# midimixer-channel.net
KiCad netlist of a schematic drawn in EAGLE
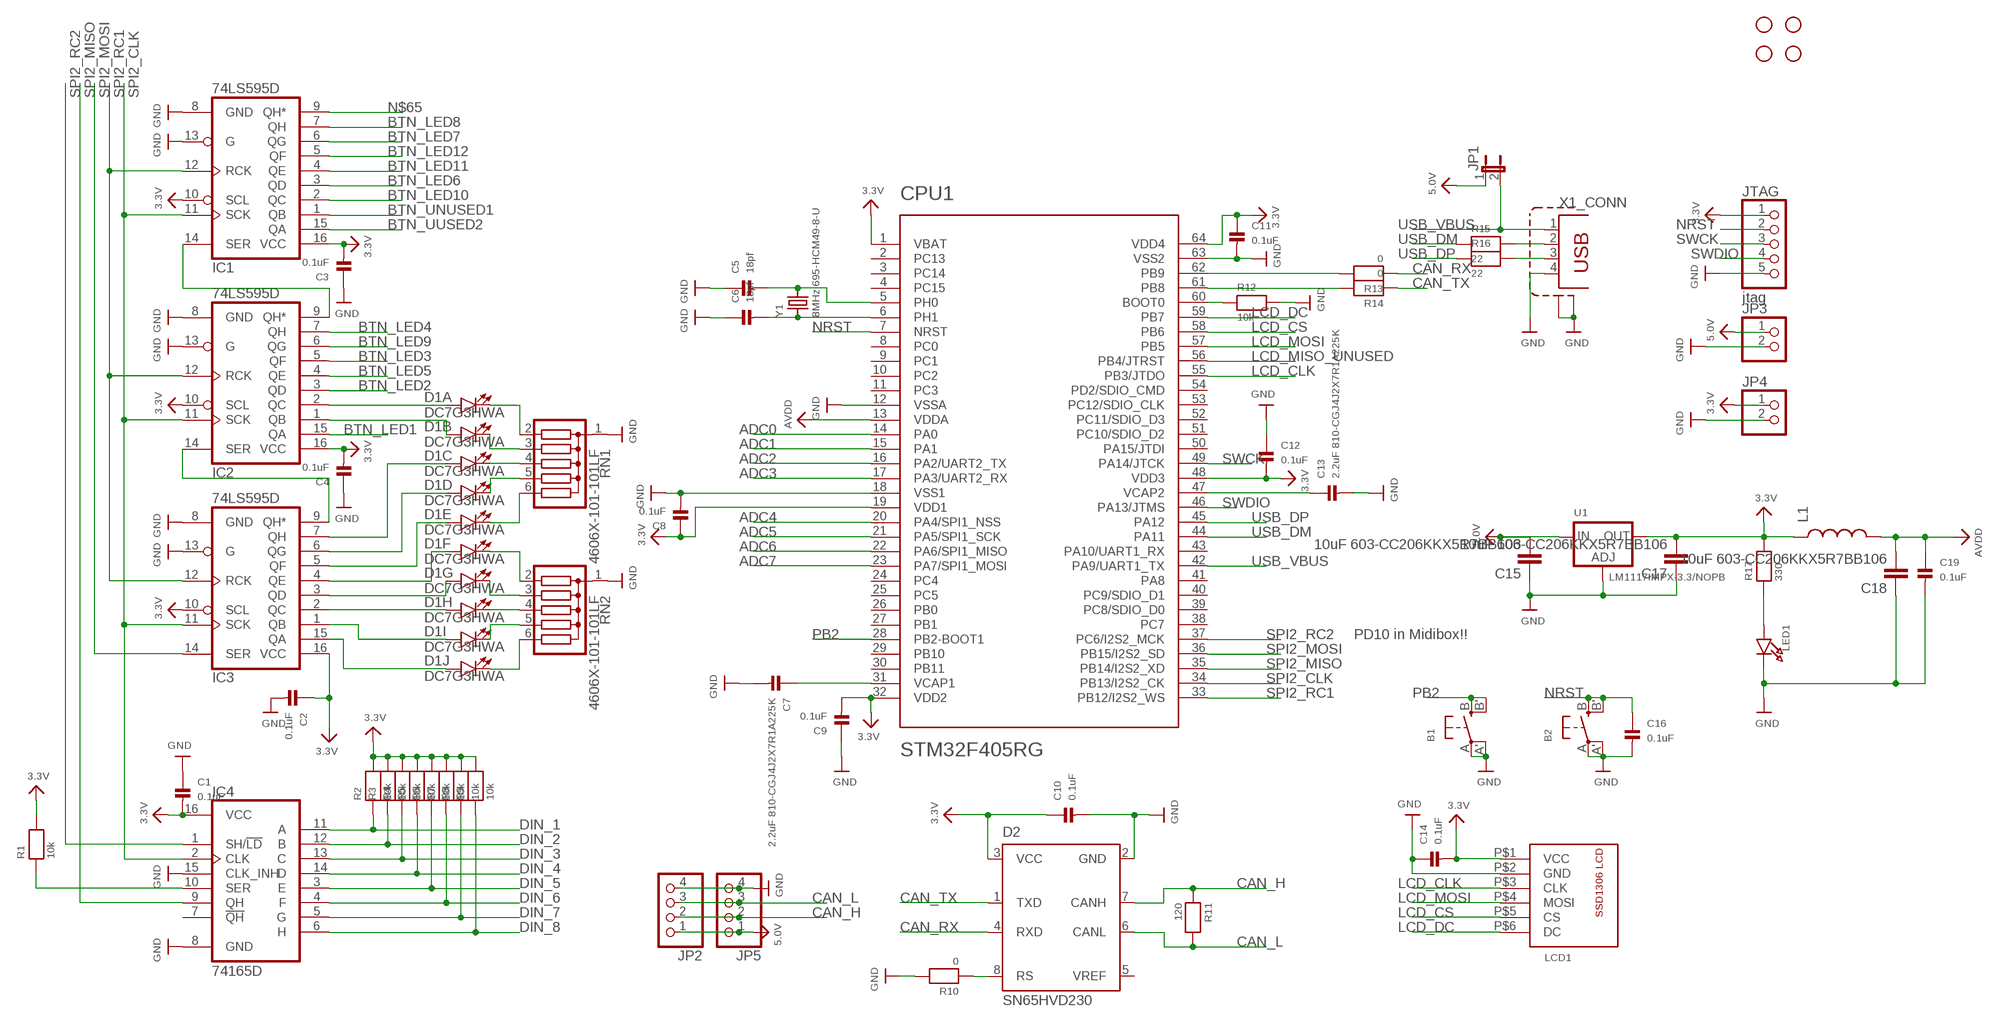
[diagram p0: schematic, sheet 1]
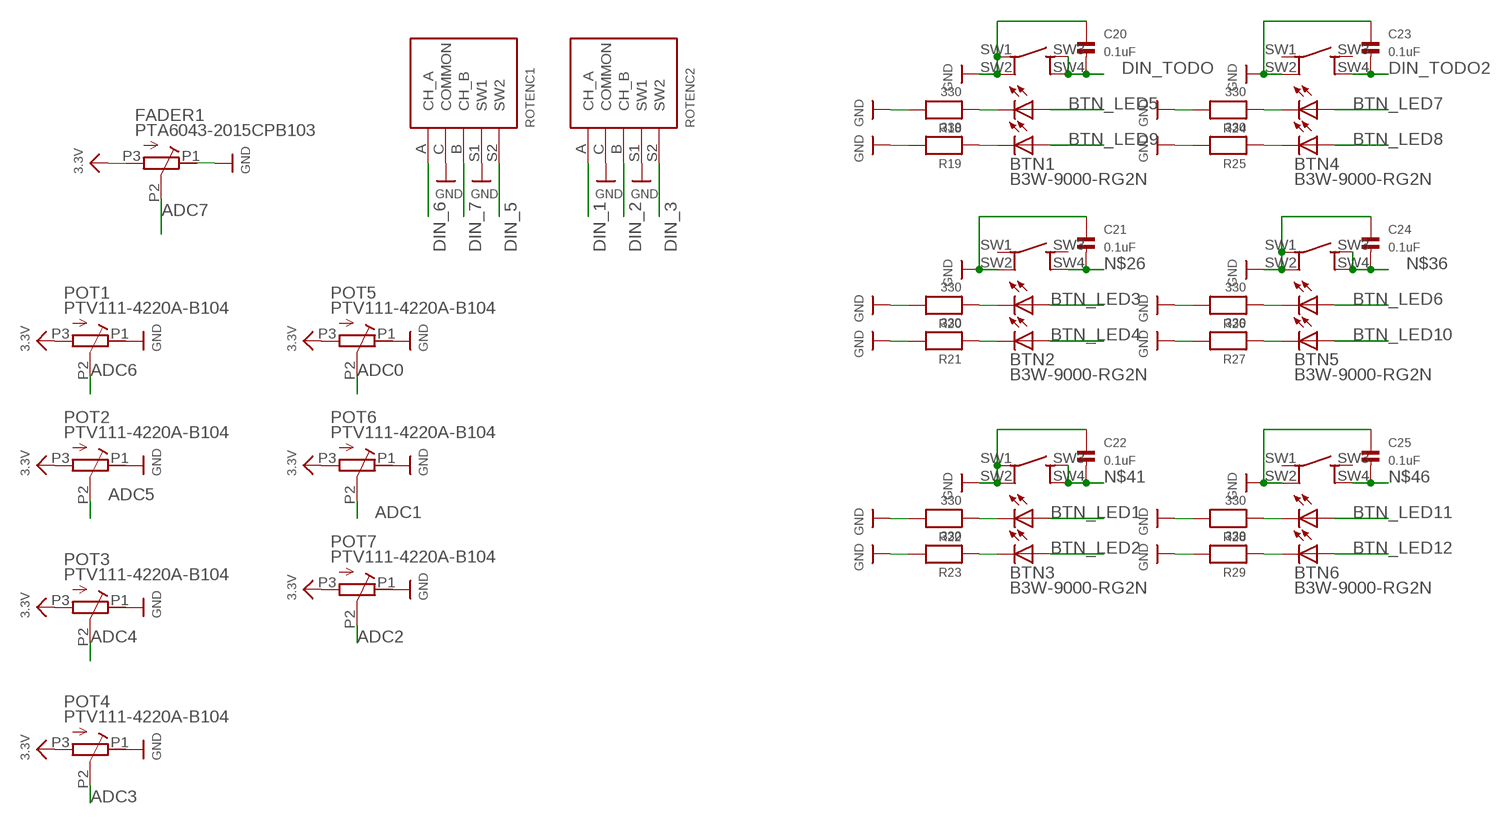
[diagram p1: schematic, sheet 2]

(export (version "E")
  (design (tool "Eeschema 10.0.6"))
  (components
    (comp (ref "B1")
      (value "SWITCH_TACT_SMT")
      (footprint "eagle-import:EVQ-Q2")
      (libsource (lib "eagle-import") (part "SWITCH_TACT_SMT"))
    )
    (comp (ref "B2")
      (value "SWITCH_TACT_SMT")
      (footprint "eagle-import:EVQ-Q2")
      (libsource (lib "eagle-import") (part "SWITCH_TACT_SMT"))
    )
    (comp (ref "C1")
      (value "0.1uF")
      (footprint "eagle-import:0603")
      (libsource (lib "eagle-import") (part "CAP_CERAMIC0603"))
    )
    (comp (ref "C2")
      (value "0.1uF")
      (footprint "eagle-import:0603")
      (libsource (lib "eagle-import") (part "CAP_CERAMIC0603"))
    )
    (comp (ref "C3")
      (value "0.1uF")
      (footprint "eagle-import:0603")
      (libsource (lib "eagle-import") (part "CAP_CERAMIC0603"))
    )
    (comp (ref "C4")
      (value "0.1uF")
      (footprint "eagle-import:0603")
      (libsource (lib "eagle-import") (part "CAP_CERAMIC0603"))
    )
    (comp (ref "C5")
      (value "18pf")
      (footprint "eagle-import:0603")
      (libsource (lib "eagle-import") (part "CAP_CERAMIC0603"))
    )
    (comp (ref "C6")
      (value "18pf")
      (footprint "eagle-import:0603")
      (libsource (lib "eagle-import") (part "CAP_CERAMIC0603"))
    )
    (comp (ref "C7")
      (value "2.2uF 810-CGJ4J2X7R1A225K")
      (footprint "eagle-import:0805")
      (libsource (lib "eagle-import") (part "CAP_CERAMIC0805"))
    )
    (comp (ref "C8")
      (value "0.1uF")
      (footprint "eagle-import:0603")
      (libsource (lib "eagle-import") (part "CAP_CERAMIC0603"))
    )
    (comp (ref "C9")
      (value "0.1uF")
      (footprint "eagle-import:0603")
      (libsource (lib "eagle-import") (part "CAP_CERAMIC0603"))
    )
    (comp (ref "C10")
      (value "0.1uF")
      (footprint "eagle-import:0603")
      (libsource (lib "eagle-import") (part "CAP_CERAMIC0603"))
    )
    (comp (ref "C11")
      (value "0.1uF")
      (footprint "eagle-import:0603")
      (libsource (lib "eagle-import") (part "CAP_CERAMIC0603"))
    )
    (comp (ref "C12")
      (value "0.1uF")
      (footprint "eagle-import:0603")
      (libsource (lib "eagle-import") (part "CAP_CERAMIC0603"))
    )
    (comp (ref "C13")
      (value "2.2uF 810-CGJ4J2X7R1A225K")
      (footprint "eagle-import:0805")
      (libsource (lib "eagle-import") (part "CAP_CERAMIC0805"))
    )
    (comp (ref "C14")
      (value "0.1uF")
      (footprint "eagle-import:0603")
      (libsource (lib "eagle-import") (part "CAP_CERAMIC0603"))
    )
    (comp (ref "C15")
      (value "10uF 603-CC206KKX5R7BB106")
      (footprint "eagle-import:1206")
      (libsource (lib "eagle-import") (part "CAP1206"))
    )
    (comp (ref "C16")
      (value "0.1uF")
      (footprint "eagle-import:0603")
      (libsource (lib "eagle-import") (part "CAP_CERAMIC0603"))
    )
    (comp (ref "C17")
      (value "10uF 603-CC206KKX5R7BB106")
      (footprint "eagle-import:1206")
      (libsource (lib "eagle-import") (part "CAP1206"))
    )
    (comp (ref "C18")
      (value "10uF 603-CC206KKX5R7BB106")
      (footprint "eagle-import:1206")
      (libsource (lib "eagle-import") (part "CAP1206"))
    )
    (comp (ref "C19")
      (value "0.1uF")
      (footprint "eagle-import:0603")
      (libsource (lib "eagle-import") (part "CAP_CERAMIC0603"))
    )
    (comp (ref "CPU1")
      (value "STM32F405RG")
      (footprint "eagle-import:TQFP64")
      (libsource (lib "eagle-import") (part "STM32F405RG"))
    )
    (comp (ref "D1")
      (value "DC7G3HWA")
      (footprint "eagle-import:LED_BARGAPH_10")
      (libsource (lib "eagle-import") (part "LED_BARGRAPH_10"))
    )
    (comp (ref "D2")
      (value "SN65HVD230")
      (footprint "eagle-import:SO8")
      (libsource (lib "eagle-import") (part "SN65HVD230"))
    )
    (comp (ref "H1")
      (value "STAND-OFF")
      (footprint "eagle-import:STAND-OFF")
      (libsource (lib "eagle-import") (part "STAND-OFF"))
    )
    (comp (ref "H2")
      (value "STAND-OFF")
      (footprint "eagle-import:STAND-OFF")
      (libsource (lib "eagle-import") (part "STAND-OFF"))
    )
    (comp (ref "H3")
      (value "STAND-OFF")
      (footprint "eagle-import:STAND-OFF")
      (libsource (lib "eagle-import") (part "STAND-OFF"))
    )
    (comp (ref "H4")
      (value "STAND-OFF")
      (footprint "eagle-import:STAND-OFF")
      (libsource (lib "eagle-import") (part "STAND-OFF"))
    )
    (comp (ref "IC1")
      (value "74LS595D")
      (footprint "eagle-import:SO16")
      (libsource (lib "eagle-import") (part "74595DLS"))
    )
    (comp (ref "IC2")
      (value "74LS595D")
      (footprint "eagle-import:SO16")
      (libsource (lib "eagle-import") (part "74595DLS"))
    )
    (comp (ref "IC3")
      (value "74LS595D")
      (footprint "eagle-import:SO16")
      (libsource (lib "eagle-import") (part "74595DLS"))
    )
    (comp (ref "IC4")
      (value "74165D")
      (footprint "eagle-import:SO16")
      (libsource (lib "eagle-import") (part "74165D"))
    )
    (comp (ref "JP1")
      (value "JUMPER2")
      (footprint "eagle-import:JUMPER2")
      (libsource (lib "eagle-import") (part "JUMPER2"))
    )
    (comp (ref "JP2")
      (value "HEADER-1X4ROUND")
      (footprint "eagle-import:1X04_ROUND")
      (libsource (lib "eagle-import") (part "HEADER-1X4ROUND"))
    )
    (comp (ref "JP3")
      (value "HEADER-1X2ROUND")
      (footprint "eagle-import:1X02_ROUND")
      (libsource (lib "eagle-import") (part "HEADER-1X2ROUND"))
    )
    (comp (ref "JP4")
      (value "HEADER-1X2ROUND")
      (footprint "eagle-import:1X02_ROUND")
      (libsource (lib "eagle-import") (part "HEADER-1X2ROUND"))
    )
    (comp (ref "JP5")
      (value "HEADER-1X4ROUND")
      (footprint "eagle-import:1X04_ROUND")
      (libsource (lib "eagle-import") (part "HEADER-1X4ROUND"))
    )
    (comp (ref "JTAG")
      (value "jtag")
      (footprint "eagle-import:1X05_ROUND_76")
      (libsource (lib "eagle-import") (part "HEADER-1X576MIL"))
    )
    (comp (ref "L1")
      (value "INDUCTOR0805")
      (footprint "eagle-import:0805")
      (libsource (lib "eagle-import") (part "INDUCTOR0805"))
    )
    (comp (ref "LCD1")
      (value "SSD1306-ALI")
      (footprint "eagle-import:SSD1306-ALI")
      (libsource (lib "eagle-import") (part "SSD1306-ALI"))
    )
    (comp (ref "LED1")
      (value "LED0603")
      (footprint "eagle-import:CHIPLED_0603")
      (libsource (lib "eagle-import") (part "LED0603"))
    )
    (comp (ref "R1")
      (value "10k")
      (footprint "eagle-import:_0603")
      (libsource (lib "eagle-import") (part "RESISTOR_0603"))
    )
    (comp (ref "R2")
      (value "10k")
      (footprint "eagle-import:_0603")
      (libsource (lib "eagle-import") (part "RESISTOR_0603"))
    )
    (comp (ref "R3")
      (value "10k")
      (footprint "eagle-import:_0603")
      (libsource (lib "eagle-import") (part "RESISTOR_0603"))
    )
    (comp (ref "R4")
      (value "10k")
      (footprint "eagle-import:_0603")
      (libsource (lib "eagle-import") (part "RESISTOR_0603"))
    )
    (comp (ref "R5")
      (value "10k")
      (footprint "eagle-import:_0603")
      (libsource (lib "eagle-import") (part "RESISTOR_0603"))
    )
    (comp (ref "R6")
      (value "10k")
      (footprint "eagle-import:_0603")
      (libsource (lib "eagle-import") (part "RESISTOR_0603"))
    )
    (comp (ref "R7")
      (value "10k")
      (footprint "eagle-import:_0603")
      (libsource (lib "eagle-import") (part "RESISTOR_0603"))
    )
    (comp (ref "R8")
      (value "10k")
      (footprint "eagle-import:_0603")
      (libsource (lib "eagle-import") (part "RESISTOR_0603"))
    )
    (comp (ref "R9")
      (value "10k")
      (footprint "eagle-import:_0603")
      (libsource (lib "eagle-import") (part "RESISTOR_0603"))
    )
    (comp (ref "R10")
      (value "0")
      (footprint "eagle-import:_0603")
      (libsource (lib "eagle-import") (part "RESISTOR_0603"))
    )
    (comp (ref "R11")
      (value "120")
      (footprint "eagle-import:_0603")
      (libsource (lib "eagle-import") (part "RESISTOR_0603"))
    )
    (comp (ref "R12")
      (value "10k")
      (footprint "eagle-import:_0603")
      (libsource (lib "eagle-import") (part "RESISTOR_0603"))
    )
    (comp (ref "R13")
      (value "0")
      (footprint "eagle-import:_0603")
      (libsource (lib "eagle-import") (part "RESISTOR_0603"))
    )
    (comp (ref "R14")
      (value "0")
      (footprint "eagle-import:_0603")
      (libsource (lib "eagle-import") (part "RESISTOR_0603"))
    )
    (comp (ref "R15")
      (value "22")
      (footprint "eagle-import:0603")
      (libsource (lib "eagle-import") (part "RESISTOR0603"))
    )
    (comp (ref "R16")
      (value "22")
      (footprint "eagle-import:0603")
      (libsource (lib "eagle-import") (part "RESISTOR0603"))
    )
    (comp (ref "R17")
      (value "330")
      (footprint "eagle-import:0603")
      (libsource (lib "eagle-import") (part "RESISTOR0603"))
    )
    (comp (ref "RN1")
      (value "4606X-101-101LF")
      (footprint "eagle-import:SIL6")
      (libsource (lib "eagle-import") (part "G05R"))
    )
    (comp (ref "RN2")
      (value "4606X-101-101LF")
      (footprint "eagle-import:SIL6")
      (libsource (lib "eagle-import") (part "G05R"))
    )
    (comp (ref "U1")
      (value "LM1117IMPX-3.3/NOPB")
      (footprint "eagle-import:SOT223-R")
      (libsource (lib "eagle-import") (part "LM1117SOT223-REFLOW"))
    )
    (comp (ref "X1")
      (value "TE-292304-1")
      (footprint "eagle-import:TE-292304-1")
      (libsource (lib "eagle-import") (part "TE-292304-1"))
    )
    (comp (ref "Y1")
      (value "8MHz 695-HCM49-8-U")
      (footprint "eagle-import:HC49UP")
      (libsource (lib "eagle-import") (part "CRYSTALSMD"))
    )
    (comp (ref "BTN1")
      (value "B3W-9000-RG2N")
      (footprint "eagle-import:B3W-9000-X2X")
      (libsource (lib "eagle-import") (part "B3W-9000-RG2N"))
    )
    (comp (ref "BTN2")
      (value "B3W-9000-RG2N")
      (footprint "eagle-import:B3W-9000-X2X")
      (libsource (lib "eagle-import") (part "B3W-9000-RG2N"))
    )
    (comp (ref "BTN3")
      (value "B3W-9000-RG2N")
      (footprint "eagle-import:B3W-9000-X2X")
      (libsource (lib "eagle-import") (part "B3W-9000-RG2N"))
    )
    (comp (ref "BTN4")
      (value "B3W-9000-RG2N")
      (footprint "eagle-import:B3W-9000-X2X")
      (libsource (lib "eagle-import") (part "B3W-9000-RG2N"))
    )
    (comp (ref "BTN5")
      (value "B3W-9000-RG2N")
      (footprint "eagle-import:B3W-9000-X2X")
      (libsource (lib "eagle-import") (part "B3W-9000-RG2N"))
    )
    (comp (ref "BTN6")
      (value "B3W-9000-RG2N")
      (footprint "eagle-import:B3W-9000-X2X")
      (libsource (lib "eagle-import") (part "B3W-9000-RG2N"))
    )
    (comp (ref "C20")
      (value "0.1uF")
      (footprint "eagle-import:0603")
      (libsource (lib "eagle-import") (part "CAP_CERAMIC0603"))
    )
    (comp (ref "C21")
      (value "0.1uF")
      (footprint "eagle-import:0603")
      (libsource (lib "eagle-import") (part "CAP_CERAMIC0603"))
    )
    (comp (ref "C22")
      (value "0.1uF")
      (footprint "eagle-import:0603")
      (libsource (lib "eagle-import") (part "CAP_CERAMIC0603"))
    )
    (comp (ref "C23")
      (value "0.1uF")
      (footprint "eagle-import:0603")
      (libsource (lib "eagle-import") (part "CAP_CERAMIC0603"))
    )
    (comp (ref "C24")
      (value "0.1uF")
      (footprint "eagle-import:0603")
      (libsource (lib "eagle-import") (part "CAP_CERAMIC0603"))
    )
    (comp (ref "C25")
      (value "0.1uF")
      (footprint "eagle-import:0603")
      (libsource (lib "eagle-import") (part "CAP_CERAMIC0603"))
    )
    (comp (ref "FADER1")
      (value "PTA6043-2015CPB103")
      (footprint "eagle-import:PTA6043-2015CPB103")
      (libsource (lib "eagle-import") (part "PTA6043-2015CPB103"))
    )
    (comp (ref "POT1")
      (value "PTV111-4220A-B104")
      (footprint "eagle-import:PTV111-4")
      (libsource (lib "eagle-import") (part "PTV111-4220A-B104"))
    )
    (comp (ref "POT2")
      (value "PTV111-4220A-B104")
      (footprint "eagle-import:PTV111-4")
      (libsource (lib "eagle-import") (part "PTV111-4220A-B104"))
    )
    (comp (ref "POT3")
      (value "PTV111-4220A-B104")
      (footprint "eagle-import:PTV111-4")
      (libsource (lib "eagle-import") (part "PTV111-4220A-B104"))
    )
    (comp (ref "POT4")
      (value "PTV111-4220A-B104")
      (footprint "eagle-import:PTV111-4")
      (libsource (lib "eagle-import") (part "PTV111-4220A-B104"))
    )
    (comp (ref "POT5")
      (value "PTV111-4220A-B104")
      (footprint "eagle-import:PTV111-4")
      (libsource (lib "eagle-import") (part "PTV111-4220A-B104"))
    )
    (comp (ref "POT6")
      (value "PTV111-4220A-B104")
      (footprint "eagle-import:PTV111-4")
      (libsource (lib "eagle-import") (part "PTV111-4220A-B104"))
    )
    (comp (ref "POT7")
      (value "PTV111-4220A-B104")
      (footprint "eagle-import:PTV111-4")
      (libsource (lib "eagle-import") (part "PTV111-4220A-B104"))
    )
    (comp (ref "R18")
      (value "330")
      (footprint "eagle-import:0603")
      (libsource (lib "eagle-import") (part "RESISTOR0603"))
    )
    (comp (ref "R19")
      (value "330")
      (footprint "eagle-import:0603")
      (libsource (lib "eagle-import") (part "RESISTOR0603"))
    )
    (comp (ref "R20")
      (value "330")
      (footprint "eagle-import:0603")
      (libsource (lib "eagle-import") (part "RESISTOR0603"))
    )
    (comp (ref "R21")
      (value "330")
      (footprint "eagle-import:0603")
      (libsource (lib "eagle-import") (part "RESISTOR0603"))
    )
    (comp (ref "R22")
      (value "330")
      (footprint "eagle-import:0603")
      (libsource (lib "eagle-import") (part "RESISTOR0603"))
    )
    (comp (ref "R23")
      (value "330")
      (footprint "eagle-import:0603")
      (libsource (lib "eagle-import") (part "RESISTOR0603"))
    )
    (comp (ref "R24")
      (value "330")
      (footprint "eagle-import:0603")
      (libsource (lib "eagle-import") (part "RESISTOR0603"))
    )
    (comp (ref "R25")
      (value "330")
      (footprint "eagle-import:0603")
      (libsource (lib "eagle-import") (part "RESISTOR0603"))
    )
    (comp (ref "R26")
      (value "330")
      (footprint "eagle-import:0603")
      (libsource (lib "eagle-import") (part "RESISTOR0603"))
    )
    (comp (ref "R27")
      (value "330")
      (footprint "eagle-import:0603")
      (libsource (lib "eagle-import") (part "RESISTOR0603"))
    )
    (comp (ref "R28")
      (value "330")
      (footprint "eagle-import:0603")
      (libsource (lib "eagle-import") (part "RESISTOR0603"))
    )
    (comp (ref "R29")
      (value "330")
      (footprint "eagle-import:0603")
      (libsource (lib "eagle-import") (part "RESISTOR0603"))
    )
    (comp (ref "ROTENC1")
      (value "PEC11-4215K-S0024")
      (footprint "eagle-import:PEC111-4XXXK-SXXXX")
      (libsource (lib "eagle-import") (part "PEC11-4215K-S0024"))
    )
    (comp (ref "ROTENC2")
      (value "PEC11-4215K-S0024")
      (footprint "eagle-import:PEC111-4XXXK-SXXXX")
      (libsource (lib "eagle-import") (part "PEC11-4215K-S0024"))
    )
  )
  (nets
    (net (code "1") (name "3.3V") (class "Default")
      (node (ref "C1") (pin "2") (pinfunction "P$2_2") (pintype "passive"))
      (node (ref "C10") (pin "1") (pinfunction "P$1_1") (pintype "passive"))
      (node (ref "C11") (pin "1") (pinfunction "P$1_1") (pintype "passive"))
      (node (ref "C12") (pin "2") (pinfunction "P$2_2") (pintype "passive"))
      (node (ref "C14") (pin "2") (pinfunction "P$2_2") (pintype "passive"))
      (node (ref "C17") (pin "2") (pinfunction "2_2") (pintype "passive"))
      (node (ref "C2") (pin "1") (pinfunction "P$1_1") (pintype "passive"))
      (node (ref "C3") (pin "2") (pinfunction "P$2_2") (pintype "passive"))
      (node (ref "C4") (pin "2") (pinfunction "P$2_2") (pintype "passive"))
      (node (ref "C8") (pin "1") (pinfunction "P$1_1") (pintype "passive"))
      (node (ref "C9") (pin "2") (pinfunction "P$2_2") (pintype "passive"))
      (node (ref "CPU1") (pin "1") (pinfunction "VBAT_1") (pintype "bidirectional"))
      (node (ref "CPU1") (pin "19") (pinfunction "VDD1_19") (pintype "bidirectional"))
      (node (ref "CPU1") (pin "32") (pinfunction "VDD2_32") (pintype "bidirectional"))
      (node (ref "CPU1") (pin "48") (pinfunction "VDD3_48") (pintype "bidirectional"))
      (node (ref "CPU1") (pin "64") (pinfunction "VDD4_64") (pintype "bidirectional"))
      (node (ref "D2") (pin "3") (pinfunction "VCC_3") (pintype "power_in"))
      (node (ref "FADER1") (pin "P3") (pinfunction "E_P3") (pintype "passive"))
      (node (ref "IC1") (pin "10") (pinfunction "SCL_10") (pintype "input"))
      (node (ref "IC1") (pin "16") (pinfunction "VCC_16") (pintype "power_in"))
      (node (ref "IC2") (pin "10") (pinfunction "SCL_10") (pintype "input"))
      (node (ref "IC2") (pin "16") (pinfunction "VCC_16") (pintype "power_in"))
      (node (ref "IC3") (pin "10") (pinfunction "SCL_10") (pintype "input"))
      (node (ref "IC3") (pin "16") (pinfunction "VCC_16") (pintype "power_in"))
      (node (ref "IC4") (pin "16") (pinfunction "VCC_16") (pintype "power_in"))
      (node (ref "JP4") (pin "1") (pinfunction "1_1") (pintype "passive"))
      (node (ref "JTAG") (pin "1") (pinfunction "1_1") (pintype "passive"))
      (node (ref "L1") (pin "1") (pinfunction "1_1") (pintype "passive"))
      (node (ref "LCD1") (pin "P$1") (pinfunction "VCC_P$1") (pintype "bidirectional"))
      (node (ref "POT1") (pin "P3") (pinfunction "E_P3") (pintype "passive"))
      (node (ref "POT2") (pin "P3") (pinfunction "E_P3") (pintype "passive"))
      (node (ref "POT3") (pin "P3") (pinfunction "E_P3") (pintype "passive"))
      (node (ref "POT4") (pin "P3") (pinfunction "E_P3") (pintype "passive"))
      (node (ref "POT5") (pin "P3") (pinfunction "E_P3") (pintype "passive"))
      (node (ref "POT6") (pin "P3") (pinfunction "E_P3") (pintype "passive"))
      (node (ref "POT7") (pin "P3") (pinfunction "E_P3") (pintype "passive"))
      (node (ref "R1") (pin "2") (pinfunction "2_2") (pintype "passive"))
      (node (ref "R17") (pin "2") (pinfunction "2_2") (pintype "passive"))
      (node (ref "R2") (pin "2") (pinfunction "2_2") (pintype "passive"))
      (node (ref "R3") (pin "2") (pinfunction "2_2") (pintype "passive"))
      (node (ref "R4") (pin "2") (pinfunction "2_2") (pintype "passive"))
      (node (ref "R5") (pin "2") (pinfunction "2_2") (pintype "passive"))
      (node (ref "R6") (pin "2") (pinfunction "2_2") (pintype "passive"))
      (node (ref "R7") (pin "2") (pinfunction "2_2") (pintype "passive"))
      (node (ref "R8") (pin "2") (pinfunction "2_2") (pintype "passive"))
      (node (ref "R9") (pin "2") (pinfunction "2_2") (pintype "passive"))
      (node (ref "U1") (pin "2") (pinfunction "OUT_2") (pintype "passive"))
    )
    (net (code "2") (name "5.0V") (class "Default")
      (node (ref "C15") (pin "2") (pinfunction "2_2") (pintype "passive"))
      (node (ref "JP1") (pin "1") (pinfunction "1_1") (pintype "passive"))
      (node (ref "JP2") (pin "1") (pinfunction "1_1") (pintype "passive"))
      (node (ref "JP3") (pin "1") (pinfunction "1_1") (pintype "passive"))
      (node (ref "JP5") (pin "1") (pinfunction "1_1") (pintype "passive"))
      (node (ref "U1") (pin "3") (pinfunction "IN_3") (pintype "input"))
    )
    (net (code "3") (name "ADC0") (class "Default")
      (node (ref "CPU1") (pin "14") (pinfunction "PA0_14") (pintype "bidirectional"))
      (node (ref "POT5") (pin "P2") (pinfunction "S_P2") (pintype "passive"))
    )
    (net (code "4") (name "ADC1") (class "Default")
      (node (ref "CPU1") (pin "15") (pinfunction "PA1_15") (pintype "bidirectional"))
      (node (ref "POT6") (pin "P2") (pinfunction "S_P2") (pintype "passive"))
    )
    (net (code "5") (name "ADC2") (class "Default")
      (node (ref "CPU1") (pin "16") (pinfunction "PA2/UART2_TX_16") (pintype "bidirectional"))
      (node (ref "POT7") (pin "P2") (pinfunction "S_P2") (pintype "passive"))
    )
    (net (code "6") (name "ADC3") (class "Default")
      (node (ref "CPU1") (pin "17") (pinfunction "PA3/UART2_RX_17") (pintype "bidirectional"))
      (node (ref "POT4") (pin "P2") (pinfunction "S_P2") (pintype "passive"))
    )
    (net (code "7") (name "ADC4") (class "Default")
      (node (ref "CPU1") (pin "20") (pinfunction "PA4/SPI1_NSS_20") (pintype "bidirectional"))
      (node (ref "POT3") (pin "P2") (pinfunction "S_P2") (pintype "passive"))
    )
    (net (code "8") (name "ADC5") (class "Default")
      (node (ref "CPU1") (pin "21") (pinfunction "PA5/SPI1_SCK_21") (pintype "bidirectional"))
      (node (ref "POT2") (pin "P2") (pinfunction "S_P2") (pintype "passive"))
    )
    (net (code "9") (name "ADC6") (class "Default")
      (node (ref "CPU1") (pin "22") (pinfunction "PA6/SPI1_MISO_22") (pintype "bidirectional"))
      (node (ref "POT1") (pin "P2") (pinfunction "S_P2") (pintype "passive"))
    )
    (net (code "10") (name "ADC7") (class "Default")
      (node (ref "CPU1") (pin "23") (pinfunction "PA7/SPI1_MOSI_23") (pintype "bidirectional"))
      (node (ref "FADER1") (pin "P2") (pinfunction "S_P2") (pintype "passive"))
    )
    (net (code "11") (name "AVDD") (class "Default")
      (node (ref "C18") (pin "2") (pinfunction "2_2") (pintype "passive"))
      (node (ref "C19") (pin "1") (pinfunction "P$1_1") (pintype "passive"))
      (node (ref "CPU1") (pin "13") (pinfunction "VDDA_13") (pintype "bidirectional"))
      (node (ref "L1") (pin "2") (pinfunction "2_2") (pintype "passive"))
    )
    (net (code "12") (name "BTN_LED1") (class "Default")
      (node (ref "BTN3") (pin "LED1+") (pinfunction "LED1+_LED1+") (pintype "passive"))
      (node (ref "IC2") (pin "15") (pinfunction "QA_15") (pintype "tri_state"))
    )
    (net (code "13") (name "BTN_LED2") (class "Default")
      (node (ref "BTN3") (pin "LED2+") (pinfunction "LED2+_LED2+") (pintype "passive"))
      (node (ref "IC2") (pin "3") (pinfunction "QD_3") (pintype "tri_state"))
    )
    (net (code "14") (name "BTN_LED3") (class "Default")
      (node (ref "BTN2") (pin "LED1+") (pinfunction "LED1+_LED1+") (pintype "passive"))
      (node (ref "IC2") (pin "5") (pinfunction "QF_5") (pintype "tri_state"))
    )
    (net (code "15") (name "BTN_LED4") (class "Default")
      (node (ref "BTN2") (pin "LED2+") (pinfunction "LED2+_LED2+") (pintype "passive"))
      (node (ref "IC2") (pin "7") (pinfunction "QH_7") (pintype "tri_state"))
    )
    (net (code "16") (name "BTN_LED5") (class "Default")
      (node (ref "BTN1") (pin "LED1+") (pinfunction "LED1+_LED1+") (pintype "passive"))
      (node (ref "IC2") (pin "4") (pinfunction "QE_4") (pintype "tri_state"))
    )
    (net (code "17") (name "BTN_LED6") (class "Default")
      (node (ref "BTN5") (pin "LED1+") (pinfunction "LED1+_LED1+") (pintype "passive"))
      (node (ref "IC1") (pin "3") (pinfunction "QD_3") (pintype "tri_state"))
    )
    (net (code "18") (name "BTN_LED7") (class "Default")
      (node (ref "BTN4") (pin "LED1+") (pinfunction "LED1+_LED1+") (pintype "passive"))
      (node (ref "IC1") (pin "6") (pinfunction "QG_6") (pintype "tri_state"))
    )
    (net (code "19") (name "BTN_LED8") (class "Default")
      (node (ref "BTN4") (pin "LED2+") (pinfunction "LED2+_LED2+") (pintype "passive"))
      (node (ref "IC1") (pin "7") (pinfunction "QH_7") (pintype "tri_state"))
    )
    (net (code "20") (name "BTN_LED9") (class "Default")
      (node (ref "BTN1") (pin "LED2+") (pinfunction "LED2+_LED2+") (pintype "passive"))
      (node (ref "IC2") (pin "6") (pinfunction "QG_6") (pintype "tri_state"))
    )
    (net (code "21") (name "BTN_LED10") (class "Default")
      (node (ref "BTN5") (pin "LED2+") (pinfunction "LED2+_LED2+") (pintype "passive"))
      (node (ref "IC1") (pin "2") (pinfunction "QC_2") (pintype "tri_state"))
    )
    (net (code "22") (name "BTN_LED11") (class "Default")
      (node (ref "BTN6") (pin "LED1+") (pinfunction "LED1+_LED1+") (pintype "passive"))
      (node (ref "IC1") (pin "4") (pinfunction "QE_4") (pintype "tri_state"))
    )
    (net (code "23") (name "BTN_LED12") (class "Default")
      (node (ref "BTN6") (pin "LED2+") (pinfunction "LED2+_LED2+") (pintype "passive"))
      (node (ref "IC1") (pin "5") (pinfunction "QF_5") (pintype "tri_state"))
    )
    (net (code "24") (name "BTN_UNUSED1") (class "Default")
      (node (ref "IC1") (pin "1") (pinfunction "QB_1") (pintype "tri_state"))
    )
    (net (code "25") (name "BTN_UUSED2") (class "Default")
      (node (ref "IC1") (pin "15") (pinfunction "QA_15") (pintype "tri_state"))
    )
    (net (code "26") (name "CAN_H") (class "Default")
      (node (ref "D2") (pin "7") (pinfunction "CANH_7") (pintype "bidirectional"))
      (node (ref "JP2") (pin "2") (pinfunction "2_2") (pintype "passive"))
      (node (ref "JP5") (pin "2") (pinfunction "2_2") (pintype "passive"))
      (node (ref "R11") (pin "1") (pinfunction "1_1") (pintype "passive"))
    )
    (net (code "27") (name "CAN_L") (class "Default")
      (node (ref "D2") (pin "6") (pinfunction "CANL_6") (pintype "bidirectional"))
      (node (ref "JP2") (pin "3") (pinfunction "3_3") (pintype "passive"))
      (node (ref "JP5") (pin "3") (pinfunction "3_3") (pintype "passive"))
      (node (ref "R11") (pin "2") (pinfunction "2_2") (pintype "passive"))
    )
    (net (code "28") (name "CAN_RX") (class "Default")
      (node (ref "D2") (pin "4") (pinfunction "RXD_4") (pintype "output"))
      (node (ref "R13") (pin "1") (pinfunction "1_1") (pintype "passive"))
    )
    (net (code "29") (name "CAN_TX") (class "Default")
      (node (ref "D2") (pin "1") (pinfunction "TXD_1") (pintype "input"))
      (node (ref "R14") (pin "1") (pinfunction "1_1") (pintype "passive"))
    )
    (net (code "30") (name "DIN_1") (class "Default")
      (node (ref "IC4") (pin "11") (pinfunction "A_11") (pintype "tri_state"))
      (node (ref "R2") (pin "1") (pinfunction "1_1") (pintype "passive"))
      (node (ref "ROTENC2") (pin "A") (pinfunction "CH_A_A") (pintype "output"))
    )
    (net (code "31") (name "DIN_2") (class "Default")
      (node (ref "IC4") (pin "12") (pinfunction "B_12") (pintype "tri_state"))
      (node (ref "R3") (pin "1") (pinfunction "1_1") (pintype "passive"))
      (node (ref "ROTENC2") (pin "B") (pinfunction "CH_B_B") (pintype "output"))
    )
    (net (code "32") (name "DIN_3") (class "Default")
      (node (ref "IC4") (pin "13") (pinfunction "C_13") (pintype "tri_state"))
      (node (ref "R4") (pin "1") (pinfunction "1_1") (pintype "passive"))
      (node (ref "ROTENC2") (pin "S2") (pinfunction "SW2_S2") (pintype "bidirectional"))
    )
    (net (code "33") (name "DIN_4") (class "Default")
      (node (ref "IC4") (pin "14") (pinfunction "D_14") (pintype "tri_state"))
      (node (ref "R5") (pin "1") (pinfunction "1_1") (pintype "passive"))
    )
    (net (code "34") (name "DIN_5") (class "Default")
      (node (ref "IC4") (pin "3") (pinfunction "E_3") (pintype "tri_state"))
      (node (ref "R6") (pin "1") (pinfunction "1_1") (pintype "passive"))
      (node (ref "ROTENC1") (pin "S2") (pinfunction "SW2_S2") (pintype "bidirectional"))
    )
    (net (code "35") (name "DIN_6") (class "Default")
      (node (ref "IC4") (pin "4") (pinfunction "F_4") (pintype "tri_state"))
      (node (ref "R7") (pin "1") (pinfunction "1_1") (pintype "passive"))
      (node (ref "ROTENC1") (pin "A") (pinfunction "CH_A_A") (pintype "output"))
    )
    (net (code "36") (name "DIN_7") (class "Default")
      (node (ref "IC4") (pin "5") (pinfunction "G_5") (pintype "tri_state"))
      (node (ref "R8") (pin "1") (pinfunction "1_1") (pintype "passive"))
      (node (ref "ROTENC1") (pin "B") (pinfunction "CH_B_B") (pintype "output"))
    )
    (net (code "37") (name "DIN_8") (class "Default")
      (node (ref "IC4") (pin "6") (pinfunction "H_6") (pintype "tri_state"))
      (node (ref "R9") (pin "1") (pinfunction "1_1") (pintype "passive"))
    )
    (net (code "38") (name "DIN_TODO") (class "Default")
      (node (ref "BTN1") (pin "SW3") (pinfunction "SW2_A_SW3") (pintype "passive"))
      (node (ref "BTN1") (pin "SW4") (pinfunction "SW2_B_SW4") (pintype "passive"))
      (node (ref "C20") (pin "2") (pinfunction "P$2_2") (pintype "passive"))
    )
    (net (code "39") (name "DIN_TODO2") (class "Default")
      (node (ref "BTN4") (pin "SW4") (pinfunction "SW2_B_SW4") (pintype "passive"))
      (node (ref "C23") (pin "2") (pinfunction "P$2_2") (pintype "passive"))
    )
    (net (code "40") (name "GND") (class "Default")
      (node (ref "B1") (pin "A") (pinfunction "P_A") (pintype "passive"))
      (node (ref "B1") (pin "A'") (pinfunction "P1_A'") (pintype "passive"))
      (node (ref "B2") (pin "A") (pinfunction "P_A") (pintype "passive"))
      (node (ref "B2") (pin "A'") (pinfunction "P1_A'") (pintype "passive"))
      (node (ref "BTN1") (pin "SW1") (pinfunction "SW1_A_SW1") (pintype "passive"))
      (node (ref "BTN1") (pin "SW2") (pinfunction "SW1_B_SW2") (pintype "passive"))
      (node (ref "BTN2") (pin "SW2") (pinfunction "SW1_B_SW2") (pintype "passive"))
      (node (ref "BTN3") (pin "SW1") (pinfunction "SW1_A_SW1") (pintype "passive"))
      (node (ref "BTN3") (pin "SW2") (pinfunction "SW1_B_SW2") (pintype "passive"))
      (node (ref "BTN4") (pin "SW2") (pinfunction "SW1_B_SW2") (pintype "passive"))
      (node (ref "BTN5") (pin "SW1") (pinfunction "SW1_A_SW1") (pintype "passive"))
      (node (ref "BTN5") (pin "SW2") (pinfunction "SW1_B_SW2") (pintype "passive"))
      (node (ref "BTN6") (pin "SW2") (pinfunction "SW1_B_SW2") (pintype "passive"))
      (node (ref "C1") (pin "1") (pinfunction "P$1_1") (pintype "passive"))
      (node (ref "C10") (pin "2") (pinfunction "P$2_2") (pintype "passive"))
      (node (ref "C11") (pin "2") (pinfunction "P$2_2") (pintype "passive"))
      (node (ref "C12") (pin "1") (pinfunction "P$1_1") (pintype "passive"))
      (node (ref "C13") (pin "2") (pinfunction "P$2_2") (pintype "passive"))
      (node (ref "C14") (pin "1") (pinfunction "P$1_1") (pintype "passive"))
      (node (ref "C15") (pin "1") (pinfunction "1_1") (pintype "passive"))
      (node (ref "C16") (pin "2") (pinfunction "P$2_2") (pintype "passive"))
      (node (ref "C17") (pin "1") (pinfunction "1_1") (pintype "passive"))
      (node (ref "C18") (pin "1") (pinfunction "1_1") (pintype "passive"))
      (node (ref "C19") (pin "2") (pinfunction "P$2_2") (pintype "passive"))
      (node (ref "C2") (pin "2") (pinfunction "P$2_2") (pintype "passive"))
      (node (ref "C20") (pin "1") (pinfunction "P$1_1") (pintype "passive"))
      (node (ref "C21") (pin "1") (pinfunction "P$1_1") (pintype "passive"))
      (node (ref "C22") (pin "1") (pinfunction "P$1_1") (pintype "passive"))
      (node (ref "C23") (pin "1") (pinfunction "P$1_1") (pintype "passive"))
      (node (ref "C24") (pin "1") (pinfunction "P$1_1") (pintype "passive"))
      (node (ref "C25") (pin "1") (pinfunction "P$1_1") (pintype "passive"))
      (node (ref "C3") (pin "1") (pinfunction "P$1_1") (pintype "passive"))
      (node (ref "C4") (pin "1") (pinfunction "P$1_1") (pintype "passive"))
      (node (ref "C5") (pin "1") (pinfunction "P$1_1") (pintype "passive"))
      (node (ref "C6") (pin "1") (pinfunction "P$1_1") (pintype "passive"))
      (node (ref "C7") (pin "2") (pinfunction "P$2_2") (pintype "passive"))
      (node (ref "C8") (pin "2") (pinfunction "P$2_2") (pintype "passive"))
      (node (ref "C9") (pin "1") (pinfunction "P$1_1") (pintype "passive"))
      (node (ref "CPU1") (pin "12") (pinfunction "VSSA_12") (pintype "bidirectional"))
      (node (ref "CPU1") (pin "18") (pinfunction "VSS1_18") (pintype "bidirectional"))
      (node (ref "CPU1") (pin "63") (pinfunction "VSS2_63") (pintype "bidirectional"))
      (node (ref "D2") (pin "2") (pinfunction "GND_2") (pintype "power_in"))
      (node (ref "FADER1") (pin "P1") (pinfunction "A_P1") (pintype "passive"))
      (node (ref "IC1") (pin "13") (pinfunction "G_13") (pintype "input"))
      (node (ref "IC1") (pin "8") (pinfunction "GND_8") (pintype "power_in"))
      (node (ref "IC2") (pin "13") (pinfunction "G_13") (pintype "input"))
      (node (ref "IC2") (pin "8") (pinfunction "GND_8") (pintype "power_in"))
      (node (ref "IC3") (pin "13") (pinfunction "G_13") (pintype "input"))
      (node (ref "IC3") (pin "8") (pinfunction "GND_8") (pintype "power_in"))
      (node (ref "IC4") (pin "15") (pinfunction "CLK_INH_15") (pintype "input"))
      (node (ref "IC4") (pin "8") (pinfunction "GND_8") (pintype "power_in"))
      (node (ref "JP2") (pin "4") (pinfunction "4_4") (pintype "passive"))
      (node (ref "JP3") (pin "2") (pinfunction "2_2") (pintype "passive"))
      (node (ref "JP4") (pin "2") (pinfunction "2_2") (pintype "passive"))
      (node (ref "JP5") (pin "4") (pinfunction "4_4") (pintype "passive"))
      (node (ref "JTAG") (pin "5") (pinfunction "5_5") (pintype "passive"))
      (node (ref "LCD1") (pin "P$2") (pinfunction "GND_P$2") (pintype "bidirectional"))
      (node (ref "LED1") (pin "C") (pinfunction "C_C") (pintype "passive"))
      (node (ref "POT1") (pin "P1") (pinfunction "A_P1") (pintype "passive"))
      (node (ref "POT2") (pin "P1") (pinfunction "A_P1") (pintype "passive"))
      (node (ref "POT3") (pin "P1") (pinfunction "A_P1") (pintype "passive"))
      (node (ref "POT4") (pin "P1") (pinfunction "A_P1") (pintype "passive"))
      (node (ref "POT5") (pin "P1") (pinfunction "A_P1") (pintype "passive"))
      (node (ref "POT6") (pin "P1") (pinfunction "A_P1") (pintype "passive"))
      (node (ref "POT7") (pin "P1") (pinfunction "A_P1") (pintype "passive"))
      (node (ref "R10") (pin "2") (pinfunction "2_2") (pintype "passive"))
      (node (ref "R12") (pin "2") (pinfunction "2_2") (pintype "passive"))
      (node (ref "R18") (pin "2") (pinfunction "2_2") (pintype "passive"))
      (node (ref "R19") (pin "2") (pinfunction "2_2") (pintype "passive"))
      (node (ref "R20") (pin "2") (pinfunction "2_2") (pintype "passive"))
      (node (ref "R21") (pin "2") (pinfunction "2_2") (pintype "passive"))
      (node (ref "R22") (pin "2") (pinfunction "2_2") (pintype "passive"))
      (node (ref "R23") (pin "2") (pinfunction "2_2") (pintype "passive"))
      (node (ref "R24") (pin "2") (pinfunction "2_2") (pintype "passive"))
      (node (ref "R25") (pin "2") (pinfunction "2_2") (pintype "passive"))
      (node (ref "R26") (pin "2") (pinfunction "2_2") (pintype "passive"))
      (node (ref "R27") (pin "2") (pinfunction "2_2") (pintype "passive"))
      (node (ref "R28") (pin "2") (pinfunction "2_2") (pintype "passive"))
      (node (ref "R29") (pin "2") (pinfunction "2_2") (pintype "passive"))
      (node (ref "RN1") (pin "1") (pinfunction "1_1") (pintype "passive"))
      (node (ref "RN2") (pin "1") (pinfunction "1_1") (pintype "passive"))
      (node (ref "ROTENC1") (pin "C") (pinfunction "COMMON_C") (pintype "input"))
      (node (ref "ROTENC1") (pin "S1") (pinfunction "SW1_S1") (pintype "bidirectional"))
      (node (ref "ROTENC2") (pin "C") (pinfunction "COMMON_C") (pintype "input"))
      (node (ref "ROTENC2") (pin "S1") (pinfunction "SW1_S1") (pintype "bidirectional"))
      (node (ref "U1") (pin "1") (pinfunction "ADJ_1") (pintype "input"))
      (node (ref "X1") (pin "4") (pinfunction "4_4") (pintype "bidirectional"))
      (node (ref "X1") (pin "P$1") (pinfunction "S1_P$1") (pintype "passive"))
      (node (ref "X1") (pin "P$2") (pinfunction "S2_P$2") (pintype "passive"))
    )
    (net (code "41") (name "LCD_CLK") (class "Default")
      (node (ref "CPU1") (pin "55") (pinfunction "PB3/JTDO_55") (pintype "bidirectional"))
      (node (ref "LCD1") (pin "P$3") (pinfunction "CLK_P$3") (pintype "bidirectional"))
    )
    (net (code "42") (name "LCD_CS") (class "Default")
      (node (ref "CPU1") (pin "58") (pinfunction "PB6_58") (pintype "bidirectional"))
      (node (ref "LCD1") (pin "P$5") (pinfunction "CS_P$5") (pintype "bidirectional"))
    )
    (net (code "43") (name "LCD_DC") (class "Default")
      (node (ref "CPU1") (pin "59") (pinfunction "PB7_59") (pintype "bidirectional"))
      (node (ref "LCD1") (pin "P$6") (pinfunction "DC_P$6") (pintype "bidirectional"))
    )
    (net (code "44") (name "LCD_MISO_UNUSED") (class "Default")
      (node (ref "CPU1") (pin "56") (pinfunction "PB4/JTRST_56") (pintype "bidirectional"))
    )
    (net (code "45") (name "LCD_MOSI") (class "Default")
      (node (ref "CPU1") (pin "57") (pinfunction "PB5_57") (pintype "bidirectional"))
      (node (ref "LCD1") (pin "P$4") (pinfunction "MOSI_P$4") (pintype "bidirectional"))
    )
    (net (code "46") (name "N$26") (class "Default")
      (node (ref "BTN2") (pin "SW4") (pinfunction "SW2_B_SW4") (pintype "passive"))
      (node (ref "C21") (pin "2") (pinfunction "P$2_2") (pintype "passive"))
    )
    (net (code "47") (name "N$36") (class "Default")
      (node (ref "BTN5") (pin "SW3") (pinfunction "SW2_A_SW3") (pintype "passive"))
      (node (ref "BTN5") (pin "SW4") (pinfunction "SW2_B_SW4") (pintype "passive"))
      (node (ref "C24") (pin "2") (pinfunction "P$2_2") (pintype "passive"))
    )
    (net (code "48") (name "N$41") (class "Default")
      (node (ref "BTN3") (pin "SW3") (pinfunction "SW2_A_SW3") (pintype "passive"))
      (node (ref "BTN3") (pin "SW4") (pinfunction "SW2_B_SW4") (pintype "passive"))
      (node (ref "C22") (pin "2") (pinfunction "P$2_2") (pintype "passive"))
    )
    (net (code "49") (name "N$46") (class "Default")
      (node (ref "BTN6") (pin "SW4") (pinfunction "SW2_B_SW4") (pintype "passive"))
      (node (ref "C25") (pin "2") (pinfunction "P$2_2") (pintype "passive"))
    )
    (net (code "50") (name "N$65") (class "Default")
      (node (ref "IC1") (pin "9") (pinfunction "QH*_9") (pintype "tri_state"))
    )
    (net (code "51") (name "NRST") (class "Default")
      (node (ref "B2") (pin "B") (pinfunction "S_B") (pintype "passive"))
      (node (ref "B2") (pin "B'") (pinfunction "S1_B'") (pintype "passive"))
      (node (ref "C16") (pin "1") (pinfunction "P$1_1") (pintype "passive"))
      (node (ref "CPU1") (pin "7") (pinfunction "NRST_7") (pintype "bidirectional"))
      (node (ref "JTAG") (pin "2") (pinfunction "2_2") (pintype "passive"))
    )
    (net (code "52") (name "Net-(BTN1-PadLED1-)") (class "Default")
      (node (ref "BTN1") (pin "LED1-") (pinfunction "LED1-_LED1-") (pintype "passive"))
      (node (ref "R18") (pin "1") (pinfunction "1_1") (pintype "passive"))
    )
    (net (code "53") (name "Net-(BTN1-PadLED2-)") (class "Default")
      (node (ref "BTN1") (pin "LED2-") (pinfunction "LED2-_LED2-") (pintype "passive"))
      (node (ref "R19") (pin "1") (pinfunction "1_1") (pintype "passive"))
    )
    (net (code "54") (name "Net-(BTN2-PadLED1-)") (class "Default")
      (node (ref "BTN2") (pin "LED1-") (pinfunction "LED1-_LED1-") (pintype "passive"))
      (node (ref "R20") (pin "1") (pinfunction "1_1") (pintype "passive"))
    )
    (net (code "55") (name "Net-(BTN2-PadLED2-)") (class "Default")
      (node (ref "BTN2") (pin "LED2-") (pinfunction "LED2-_LED2-") (pintype "passive"))
      (node (ref "R21") (pin "1") (pinfunction "1_1") (pintype "passive"))
    )
    (net (code "56") (name "Net-(BTN3-PadLED1-)") (class "Default")
      (node (ref "BTN3") (pin "LED1-") (pinfunction "LED1-_LED1-") (pintype "passive"))
      (node (ref "R22") (pin "1") (pinfunction "1_1") (pintype "passive"))
    )
    (net (code "57") (name "Net-(BTN3-PadLED2-)") (class "Default")
      (node (ref "BTN3") (pin "LED2-") (pinfunction "LED2-_LED2-") (pintype "passive"))
      (node (ref "R23") (pin "1") (pinfunction "1_1") (pintype "passive"))
    )
    (net (code "58") (name "Net-(BTN4-PadLED1-)") (class "Default")
      (node (ref "BTN4") (pin "LED1-") (pinfunction "LED1-_LED1-") (pintype "passive"))
      (node (ref "R24") (pin "1") (pinfunction "1_1") (pintype "passive"))
    )
    (net (code "59") (name "Net-(BTN4-PadLED2-)") (class "Default")
      (node (ref "BTN4") (pin "LED2-") (pinfunction "LED2-_LED2-") (pintype "passive"))
      (node (ref "R25") (pin "1") (pinfunction "1_1") (pintype "passive"))
    )
    (net (code "60") (name "Net-(BTN5-PadLED1-)") (class "Default")
      (node (ref "BTN5") (pin "LED1-") (pinfunction "LED1-_LED1-") (pintype "passive"))
      (node (ref "R26") (pin "1") (pinfunction "1_1") (pintype "passive"))
    )
    (net (code "61") (name "Net-(BTN5-PadLED2-)") (class "Default")
      (node (ref "BTN5") (pin "LED2-") (pinfunction "LED2-_LED2-") (pintype "passive"))
      (node (ref "R27") (pin "1") (pinfunction "1_1") (pintype "passive"))
    )
    (net (code "62") (name "Net-(BTN6-PadLED1-)") (class "Default")
      (node (ref "BTN6") (pin "LED1-") (pinfunction "LED1-_LED1-") (pintype "passive"))
      (node (ref "R28") (pin "1") (pinfunction "1_1") (pintype "passive"))
    )
    (net (code "63") (name "Net-(BTN6-PadLED2-)") (class "Default")
      (node (ref "BTN6") (pin "LED2-") (pinfunction "LED2-_LED2-") (pintype "passive"))
      (node (ref "R29") (pin "1") (pinfunction "1_1") (pintype "passive"))
    )
    (net (code "64") (name "Net-(C5-P$2)") (class "Default")
      (node (ref "C5") (pin "2") (pinfunction "P$2_2") (pintype "passive"))
      (node (ref "CPU1") (pin "5") (pinfunction "PH0_5") (pintype "bidirectional"))
      (node (ref "Y1") (pin "2") (pinfunction "2_2") (pintype "passive"))
    )
    (net (code "65") (name "Net-(C6-P$2)") (class "Default")
      (node (ref "C6") (pin "2") (pinfunction "P$2_2") (pintype "passive"))
      (node (ref "CPU1") (pin "6") (pinfunction "PH1_6") (pintype "bidirectional"))
      (node (ref "Y1") (pin "1") (pinfunction "1_1") (pintype "passive"))
    )
    (net (code "66") (name "Net-(C7-P$1)") (class "Default")
      (node (ref "C7") (pin "1") (pinfunction "P$1_1") (pintype "passive"))
      (node (ref "CPU1") (pin "31") (pinfunction "VCAP1_31") (pintype "bidirectional"))
    )
    (net (code "67") (name "Net-(C13-P$1)") (class "Default")
      (node (ref "C13") (pin "1") (pinfunction "P$1_1") (pintype "passive"))
      (node (ref "CPU1") (pin "47") (pinfunction "VCAP2_47") (pintype "bidirectional"))
    )
    (net (code "68") (name "Net-(CPU1-BOOT0)") (class "Default")
      (node (ref "CPU1") (pin "60") (pinfunction "BOOT0_60") (pintype "bidirectional"))
      (node (ref "R12") (pin "1") (pinfunction "1_1") (pintype "passive"))
    )
    (net (code "69") (name "Net-(CPU1-PB8)") (class "Default")
      (node (ref "CPU1") (pin "61") (pinfunction "PB8_61") (pintype "bidirectional"))
      (node (ref "R14") (pin "2") (pinfunction "2_2") (pintype "passive"))
    )
    (net (code "70") (name "Net-(CPU1-PB9)") (class "Default")
      (node (ref "CPU1") (pin "62") (pinfunction "PB9_62") (pintype "bidirectional"))
      (node (ref "R13") (pin "2") (pinfunction "2_2") (pintype "passive"))
    )
    (net (code "71") (name "Net-(D1A-A)") (class "Default")
      (node (ref "D1") (pin "1") (pinfunction "A_1") (pintype "passive"))
      (node (ref "IC2") (pin "2") (pinfunction "QC_2") (pintype "tri_state"))
    )
    (net (code "72") (name "Net-(D1A-C)") (class "Default")
      (node (ref "D1") (pin "20") (pinfunction "C_20") (pintype "passive"))
      (node (ref "RN1") (pin "2") (pinfunction "2_2") (pintype "passive"))
    )
    (net (code "73") (name "Net-(D1B-A)") (class "Default")
      (node (ref "D1") (pin "2") (pinfunction "A_2") (pintype "passive"))
      (node (ref "IC2") (pin "1") (pinfunction "QB_1") (pintype "tri_state"))
    )
    (net (code "74") (name "Net-(D1B-C)") (class "Default")
      (node (ref "D1") (pin "19") (pinfunction "C_19") (pintype "passive"))
      (node (ref "RN1") (pin "3") (pinfunction "3_3") (pintype "passive"))
    )
    (net (code "75") (name "Net-(D1C-A)") (class "Default")
      (node (ref "D1") (pin "3") (pinfunction "A_3") (pintype "passive"))
      (node (ref "IC3") (pin "7") (pinfunction "QH_7") (pintype "tri_state"))
    )
    (net (code "76") (name "Net-(D1C-C)") (class "Default")
      (node (ref "D1") (pin "18") (pinfunction "C_18") (pintype "passive"))
      (node (ref "RN1") (pin "4") (pinfunction "4_4") (pintype "passive"))
    )
    (net (code "77") (name "Net-(D1D-A)") (class "Default")
      (node (ref "D1") (pin "4") (pinfunction "A_4") (pintype "passive"))
      (node (ref "IC3") (pin "6") (pinfunction "QG_6") (pintype "tri_state"))
    )
    (net (code "78") (name "Net-(D1D-C)") (class "Default")
      (node (ref "D1") (pin "17") (pinfunction "C_17") (pintype "passive"))
      (node (ref "RN1") (pin "5") (pinfunction "5_5") (pintype "passive"))
    )
    (net (code "79") (name "Net-(D1E-A)") (class "Default")
      (node (ref "D1") (pin "5") (pinfunction "A_5") (pintype "passive"))
      (node (ref "IC3") (pin "5") (pinfunction "QF_5") (pintype "tri_state"))
    )
    (net (code "80") (name "Net-(D1E-C)") (class "Default")
      (node (ref "D1") (pin "16") (pinfunction "C_16") (pintype "passive"))
      (node (ref "RN1") (pin "6") (pinfunction "6_6") (pintype "passive"))
    )
    (net (code "81") (name "Net-(D1F-A)") (class "Default")
      (node (ref "D1") (pin "6") (pinfunction "A_6") (pintype "passive"))
      (node (ref "IC3") (pin "4") (pinfunction "QE_4") (pintype "tri_state"))
    )
    (net (code "82") (name "Net-(D1F-C)") (class "Default")
      (node (ref "D1") (pin "15") (pinfunction "C_15") (pintype "passive"))
      (node (ref "RN2") (pin "2") (pinfunction "2_2") (pintype "passive"))
    )
    (net (code "83") (name "Net-(D1G-A)") (class "Default")
      (node (ref "D1") (pin "7") (pinfunction "A_7") (pintype "passive"))
      (node (ref "IC3") (pin "3") (pinfunction "QD_3") (pintype "tri_state"))
    )
    (net (code "84") (name "Net-(D1G-C)") (class "Default")
      (node (ref "D1") (pin "14") (pinfunction "C_14") (pintype "passive"))
      (node (ref "RN2") (pin "3") (pinfunction "3_3") (pintype "passive"))
    )
    (net (code "85") (name "Net-(D1H-A)") (class "Default")
      (node (ref "D1") (pin "8") (pinfunction "A_8") (pintype "passive"))
      (node (ref "IC3") (pin "2") (pinfunction "QC_2") (pintype "tri_state"))
    )
    (net (code "86") (name "Net-(D1H-C)") (class "Default")
      (node (ref "D1") (pin "13") (pinfunction "C_13") (pintype "passive"))
      (node (ref "RN2") (pin "4") (pinfunction "4_4") (pintype "passive"))
    )
    (net (code "87") (name "Net-(D1I-A)") (class "Default")
      (node (ref "D1") (pin "9") (pinfunction "A_9") (pintype "passive"))
      (node (ref "IC3") (pin "1") (pinfunction "QB_1") (pintype "tri_state"))
    )
    (net (code "88") (name "Net-(D1I-C)") (class "Default")
      (node (ref "D1") (pin "12") (pinfunction "C_12") (pintype "passive"))
      (node (ref "RN2") (pin "5") (pinfunction "5_5") (pintype "passive"))
    )
    (net (code "89") (name "Net-(D1J-A)") (class "Default")
      (node (ref "D1") (pin "10") (pinfunction "A_10") (pintype "passive"))
      (node (ref "IC3") (pin "15") (pinfunction "QA_15") (pintype "tri_state"))
    )
    (net (code "90") (name "Net-(D1J-C)") (class "Default")
      (node (ref "D1") (pin "11") (pinfunction "C_11") (pintype "passive"))
      (node (ref "RN2") (pin "6") (pinfunction "6_6") (pintype "passive"))
    )
    (net (code "91") (name "Net-(D2-RS)") (class "Default")
      (node (ref "D2") (pin "8") (pinfunction "RS_8") (pintype "input"))
      (node (ref "R10") (pin "1") (pinfunction "1_1") (pintype "passive"))
    )
    (net (code "92") (name "Net-(IC1-SER)") (class "Default")
      (node (ref "IC1") (pin "14") (pinfunction "SER_14") (pintype "input"))
      (node (ref "IC2") (pin "9") (pinfunction "QH*_9") (pintype "tri_state"))
    )
    (net (code "93") (name "Net-(IC2-SER)") (class "Default")
      (node (ref "IC2") (pin "14") (pinfunction "SER_14") (pintype "input"))
      (node (ref "IC3") (pin "9") (pinfunction "QH*_9") (pintype "tri_state"))
    )
    (net (code "94") (name "Net-(IC4-SER)") (class "Default")
      (node (ref "IC4") (pin "10") (pinfunction "SER_10") (pintype "input"))
      (node (ref "R1") (pin "1") (pinfunction "1_1") (pintype "passive"))
    )
    (net (code "95") (name "Net-(LED1-PadA)") (class "Default")
      (node (ref "LED1") (pin "A") (pinfunction "A_A") (pintype "passive"))
      (node (ref "R17") (pin "1") (pinfunction "1_1") (pintype "passive"))
    )
    (net (code "96") (name "Net-(R15-Pad2)") (class "Default")
      (node (ref "R15") (pin "2") (pinfunction "2_2") (pintype "passive"))
      (node (ref "X1") (pin "2") (pinfunction "2_2") (pintype "bidirectional"))
    )
    (net (code "97") (name "Net-(R16-Pad2)") (class "Default")
      (node (ref "R16") (pin "2") (pinfunction "2_2") (pintype "passive"))
      (node (ref "X1") (pin "3") (pinfunction "3_3") (pintype "bidirectional"))
    )
    (net (code "98") (name "PB2") (class "Default")
      (node (ref "B1") (pin "B") (pinfunction "S_B") (pintype "passive"))
      (node (ref "B1") (pin "B'") (pinfunction "S1_B'") (pintype "passive"))
      (node (ref "CPU1") (pin "28") (pinfunction "PB2-BOOT1_28") (pintype "bidirectional"))
    )
    (net (code "99") (name "SPI2_CLK") (class "Default")
      (node (ref "CPU1") (pin "34") (pinfunction "PB13/I2S2_CK_34") (pintype "bidirectional"))
      (node (ref "IC1") (pin "11") (pinfunction "SCK_11") (pintype "input"))
      (node (ref "IC2") (pin "11") (pinfunction "SCK_11") (pintype "input"))
      (node (ref "IC3") (pin "11") (pinfunction "SCK_11") (pintype "input"))
      (node (ref "IC4") (pin "2") (pinfunction "CLK_2") (pintype "input"))
    )
    (net (code "100") (name "SPI2_MISO") (class "Default")
      (node (ref "CPU1") (pin "35") (pinfunction "PB14/I2S2_XD_35") (pintype "bidirectional"))
      (node (ref "IC4") (pin "9") (pinfunction "QH_9") (pintype "tri_state"))
    )
    (net (code "101") (name "SPI2_MOSI") (class "Default")
      (node (ref "CPU1") (pin "36") (pinfunction "PB15/I2S2_SD_36") (pintype "bidirectional"))
      (node (ref "IC3") (pin "14") (pinfunction "SER_14") (pintype "input"))
    )
    (net (code "102") (name "SPI2_RC1") (class "Default")
      (node (ref "CPU1") (pin "33") (pinfunction "PB12/I2S2_WS_33") (pintype "bidirectional"))
      (node (ref "IC1") (pin "12") (pinfunction "RCK_12") (pintype "input"))
      (node (ref "IC2") (pin "12") (pinfunction "RCK_12") (pintype "input"))
      (node (ref "IC3") (pin "12") (pinfunction "RCK_12") (pintype "input"))
    )
    (net (code "103") (name "SPI2_RC2") (class "Default")
      (node (ref "CPU1") (pin "37") (pinfunction "PC6/I2S2_MCK_37") (pintype "bidirectional"))
      (node (ref "IC4") (pin "1") (pinfunction "SH/~{LD}_1") (pintype "input"))
    )
    (net (code "104") (name "SWCK") (class "Default")
      (node (ref "CPU1") (pin "49") (pinfunction "PA14/JTCK_49") (pintype "bidirectional"))
      (node (ref "JTAG") (pin "3") (pinfunction "3_3") (pintype "passive"))
    )
    (net (code "105") (name "SWDIO") (class "Default")
      (node (ref "CPU1") (pin "46") (pinfunction "PA13/JTMS_46") (pintype "bidirectional"))
      (node (ref "JTAG") (pin "4") (pinfunction "4_4") (pintype "passive"))
    )
    (net (code "106") (name "USB_DM") (class "Default")
      (node (ref "CPU1") (pin "44") (pinfunction "PA11_44") (pintype "bidirectional"))
      (node (ref "R15") (pin "1") (pinfunction "1_1") (pintype "passive"))
    )
    (net (code "107") (name "USB_DP") (class "Default")
      (node (ref "CPU1") (pin "45") (pinfunction "PA12_45") (pintype "bidirectional"))
      (node (ref "R16") (pin "1") (pinfunction "1_1") (pintype "passive"))
    )
    (net (code "108") (name "USB_VBUS") (class "Default")
      (node (ref "CPU1") (pin "42") (pinfunction "PA9/UART1_TX_42") (pintype "bidirectional"))
      (node (ref "JP1") (pin "2") (pinfunction "2_2") (pintype "passive"))
      (node (ref "X1") (pin "1") (pinfunction "1_1") (pintype "bidirectional"))
    )
    (net (code "109") (name "unconnected-(BTN2-SW1_A-PadSW1)") (class "Default")
      (node (ref "BTN2") (pin "SW1") (pinfunction "SW1_A_SW1") (pintype "passive"))
    )
    (net (code "110") (name "unconnected-(BTN2-SW2_A-PadSW3)") (class "Default")
      (node (ref "BTN2") (pin "SW3") (pinfunction "SW2_A_SW3") (pintype "passive"))
    )
    (net (code "111") (name "unconnected-(BTN4-SW1_A-PadSW1)") (class "Default")
      (node (ref "BTN4") (pin "SW1") (pinfunction "SW1_A_SW1") (pintype "passive"))
    )
    (net (code "112") (name "unconnected-(BTN4-SW2_A-PadSW3)") (class "Default")
      (node (ref "BTN4") (pin "SW3") (pinfunction "SW2_A_SW3") (pintype "passive"))
    )
    (net (code "113") (name "unconnected-(BTN6-SW1_A-PadSW1)") (class "Default")
      (node (ref "BTN6") (pin "SW1") (pinfunction "SW1_A_SW1") (pintype "passive"))
    )
    (net (code "114") (name "unconnected-(BTN6-SW2_A-PadSW3)") (class "Default")
      (node (ref "BTN6") (pin "SW3") (pinfunction "SW2_A_SW3") (pintype "passive"))
    )
    (net (code "115") (name "unconnected-(CPU1-PA8-Pad41)") (class "Default")
      (node (ref "CPU1") (pin "41") (pinfunction "PA8_41") (pintype "bidirectional"))
    )
    (net (code "116") (name "unconnected-(CPU1-PA10{slash}UART1_RX-Pad43)") (class "Default")
      (node (ref "CPU1") (pin "43") (pinfunction "PA10/UART1_RX_43") (pintype "bidirectional"))
    )
    (net (code "117") (name "unconnected-(CPU1-PA15{slash}JTDI-Pad50)") (class "Default")
      (node (ref "CPU1") (pin "50") (pinfunction "PA15/JTDI_50") (pintype "bidirectional"))
    )
    (net (code "118") (name "unconnected-(CPU1-PB0-Pad26)") (class "Default")
      (node (ref "CPU1") (pin "26") (pinfunction "PB0_26") (pintype "bidirectional"))
    )
    (net (code "119") (name "unconnected-(CPU1-PB1-Pad27)") (class "Default")
      (node (ref "CPU1") (pin "27") (pinfunction "PB1_27") (pintype "bidirectional"))
    )
    (net (code "120") (name "unconnected-(CPU1-PB10-Pad29)") (class "Default")
      (node (ref "CPU1") (pin "29") (pinfunction "PB10_29") (pintype "bidirectional"))
    )
    (net (code "121") (name "unconnected-(CPU1-PB11-Pad30)") (class "Default")
      (node (ref "CPU1") (pin "30") (pinfunction "PB11_30") (pintype "bidirectional"))
    )
    (net (code "122") (name "unconnected-(CPU1-PC0-Pad8)") (class "Default")
      (node (ref "CPU1") (pin "8") (pinfunction "PC0_8") (pintype "bidirectional"))
    )
    (net (code "123") (name "unconnected-(CPU1-PC1-Pad9)") (class "Default")
      (node (ref "CPU1") (pin "9") (pinfunction "PC1_9") (pintype "bidirectional"))
    )
    (net (code "124") (name "unconnected-(CPU1-PC2-Pad10)") (class "Default")
      (node (ref "CPU1") (pin "10") (pinfunction "PC2_10") (pintype "bidirectional"))
    )
    (net (code "125") (name "unconnected-(CPU1-PC3-Pad11)") (class "Default")
      (node (ref "CPU1") (pin "11") (pinfunction "PC3_11") (pintype "bidirectional"))
    )
    (net (code "126") (name "unconnected-(CPU1-PC4-Pad24)") (class "Default")
      (node (ref "CPU1") (pin "24") (pinfunction "PC4_24") (pintype "bidirectional"))
    )
    (net (code "127") (name "unconnected-(CPU1-PC5-Pad25)") (class "Default")
      (node (ref "CPU1") (pin "25") (pinfunction "PC5_25") (pintype "bidirectional"))
    )
    (net (code "128") (name "unconnected-(CPU1-PC7-Pad38)") (class "Default")
      (node (ref "CPU1") (pin "38") (pinfunction "PC7_38") (pintype "bidirectional"))
    )
    (net (code "129") (name "unconnected-(CPU1-PC8{slash}SDIO_D0-Pad39)") (class "Default")
      (node (ref "CPU1") (pin "39") (pinfunction "PC8/SDIO_D0_39") (pintype "bidirectional"))
    )
    (net (code "130") (name "unconnected-(CPU1-PC9{slash}SDIO_D1-Pad40)") (class "Default")
      (node (ref "CPU1") (pin "40") (pinfunction "PC9/SDIO_D1_40") (pintype "bidirectional"))
    )
    (net (code "131") (name "unconnected-(CPU1-PC10{slash}SDIO_D2-Pad51)") (class "Default")
      (node (ref "CPU1") (pin "51") (pinfunction "PC10/SDIO_D2_51") (pintype "bidirectional"))
    )
    (net (code "132") (name "unconnected-(CPU1-PC11{slash}SDIO_D3-Pad52)") (class "Default")
      (node (ref "CPU1") (pin "52") (pinfunction "PC11/SDIO_D3_52") (pintype "bidirectional"))
    )
    (net (code "133") (name "unconnected-(CPU1-PC12{slash}SDIO_CLK-Pad53)") (class "Default")
      (node (ref "CPU1") (pin "53") (pinfunction "PC12/SDIO_CLK_53") (pintype "bidirectional"))
    )
    (net (code "134") (name "unconnected-(CPU1-PC13-Pad2)") (class "Default")
      (node (ref "CPU1") (pin "2") (pinfunction "PC13_2") (pintype "bidirectional"))
    )
    (net (code "135") (name "unconnected-(CPU1-PC14-Pad3)") (class "Default")
      (node (ref "CPU1") (pin "3") (pinfunction "PC14_3") (pintype "bidirectional"))
    )
    (net (code "136") (name "unconnected-(CPU1-PC15-Pad4)") (class "Default")
      (node (ref "CPU1") (pin "4") (pinfunction "PC15_4") (pintype "bidirectional"))
    )
    (net (code "137") (name "unconnected-(CPU1-PD2{slash}SDIO_CMD-Pad54)") (class "Default")
      (node (ref "CPU1") (pin "54") (pinfunction "PD2/SDIO_CMD_54") (pintype "bidirectional"))
    )
    (net (code "138") (name "unconnected-(D2-VREF-Pad5)") (class "Default")
      (node (ref "D2") (pin "5") (pinfunction "VREF_5") (pintype "output"))
    )
    (net (code "139") (name "unconnected-(IC4-~{QH}-Pad7)") (class "Default")
      (node (ref "IC4") (pin "7") (pinfunction "~{QH}_7") (pintype "input"))
    )
  )
)
